# Output_Driver.net
KiCad netlist of a schematic drawn in Altium Designer
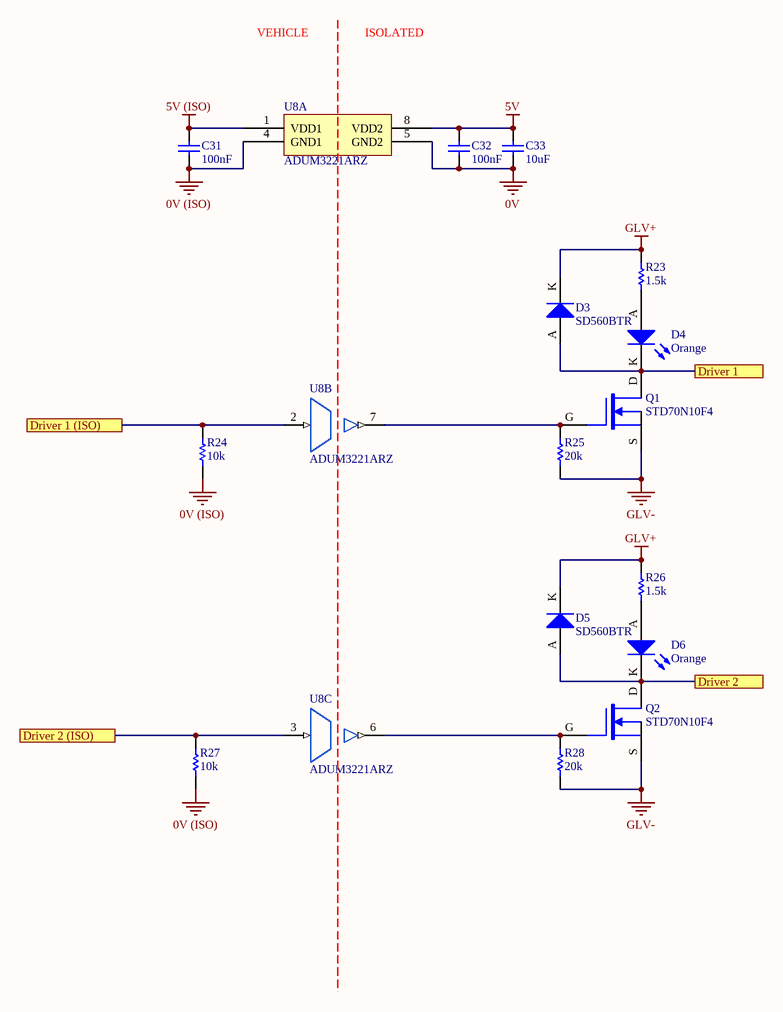
[diagram p0: Output Driver.SchDoc]

(export (version "E")
  (design (tool "Eeschema 10.0.6"))
  (components
    (comp (ref "C31")
      (value "100nF")
      (footprint "0805")
      (fields
        (field (name "PART NUMBER") "GCM21BR71E104KA37L")
        (field (name "TOLERANCE") "10%")
        (field (name "MANUFACTURER") "muRata")
      )
      (libsource (lib "ts_20-standard-library") (part "Capacitor"))
    )
    (comp (ref "C32")
      (value "100nF")
      (footprint "0805")
      (fields
        (field (name "PART NUMBER") "GCM21BR71E104KA37L")
        (field (name "TOLERANCE") "10%")
        (field (name "MANUFACTURER") "muRata")
      )
      (libsource (lib "ts_20-standard-library") (part "Capacitor"))
    )
    (comp (ref "C33")
      (value "10uF")
      (footprint "0805")
      (fields
        (field (name "PART NUMBER") "GRM21BR6YA106KE43L")
        (field (name "TOLERANCE") "10%")
        (field (name "MANUFACTURER") "muRata")
      )
      (libsource (lib "ts_20-standard-library") (part "Capacitor"))
    )
    (comp (ref "D3")
      (value "SD560BTR")
      (footprint "SMB Diode")
      (description "1.2V_F 600V 5A SMB")
      (fields
        (field (name "MANUFACTURER") "SMC Diode Solutions")
        (field (name "DIGIKEY PART NUMBER") "1655-1530-2-ND")
      )
      (libsource (lib "ts_20-standard-library") (part "Diode"))
    )
    (comp (ref "D4")
      (value "Orange")
      (footprint "0805 LED")
      (description "Orange LED Indication - Discrete 1.75V 0805 (2012 Metric)")
      (fields (field (name "PART NUMBER") "SML-211DTT86") (field (name "MANUFACTURER") "ROHM Semiconductor"))
      (libsource (lib "ts_20-standard-library") (part "LED"))
    )
    (comp (ref "D5")
      (value "SD560BTR")
      (footprint "SMB Diode")
      (description "1.2V_F 600V 5A SMB")
      (fields
        (field (name "MANUFACTURER") "SMC Diode Solutions")
        (field (name "DIGIKEY PART NUMBER") "1655-1530-2-ND")
      )
      (libsource (lib "ts_20-standard-library") (part "Diode"))
    )
    (comp (ref "D6")
      (value "Orange")
      (footprint "0805 LED")
      (description "Orange LED Indication - Discrete 1.75V 0805 (2012 Metric)")
      (fields (field (name "PART NUMBER") "SML-211DTT86") (field (name "MANUFACTURER") "ROHM Semiconductor"))
      (libsource (lib "ts_20-standard-library") (part "LED"))
    )
    (comp (ref "Q1")
      (value "STD70N10F4")
      (footprint "SOT-343_N")
      (description "N-Channel 100V 60A (Tc) 125W (Tc) Surface Mount DPAK")
      (fields
        (field (name "MANUFACTURER") "STMicroelectronics")
        (field (name "DIGIKEY PART NUMBER") "497-8806-2-ND")
        (field (name "PUBLISHER") "Altium Limited")
      )
      (libsource (lib "ts_20-standard-library") (part "MOSFET-N"))
    )
    (comp (ref "Q2")
      (value "STD70N10F4")
      (footprint "SOT-343_N")
      (description "N-Channel 100V 60A (Tc) 125W (Tc) Surface Mount DPAK")
      (fields
        (field (name "MANUFACTURER") "STMicroelectronics")
        (field (name "DIGIKEY PART NUMBER") "497-8806-2-ND")
        (field (name "PUBLISHER") "Altium Limited")
      )
      (libsource (lib "ts_20-standard-library") (part "MOSFET-N"))
    )
    (comp (ref "R23")
      (value "1.5k")
      (footprint "0805")
      (fields
        (field (name "PART NUMBER") "RC0805FR071K5L")
        (field (name "MANUFACTURER") "YAGEO")
        (field (name "TOLERANCE") "0.01")
      )
      (libsource (lib "ts_20-standard-library") (part "Resistor"))
    )
    (comp (ref "R24")
      (value "10k")
      (footprint "0805")
      (fields
        (field (name "PART NUMBER") "RC0805FR0710KL")
        (field (name "MANUFACTURER") "YAGEO")
        (field (name "TOLERANCE") "0.01")
      )
      (libsource (lib "ts_20-standard-library") (part "Resistor"))
    )
    (comp (ref "R25")
      (value "20k")
      (footprint "0805")
      (fields
        (field (name "PART NUMBER") "RC0805FR0720KL")
        (field (name "MANUFACTURER") "YAGEO")
        (field (name "TOLERANCE") "0.01")
      )
      (libsource (lib "ts_20-standard-library") (part "Resistor"))
    )
    (comp (ref "R26")
      (value "1.5k")
      (footprint "0805")
      (fields
        (field (name "PART NUMBER") "RC0805FR071K5L")
        (field (name "MANUFACTURER") "YAGEO")
        (field (name "TOLERANCE") "0.01")
      )
      (libsource (lib "ts_20-standard-library") (part "Resistor"))
    )
    (comp (ref "R27")
      (value "10k")
      (footprint "0805")
      (fields
        (field (name "PART NUMBER") "RC0805FR0710KL")
        (field (name "MANUFACTURER") "YAGEO")
        (field (name "TOLERANCE") "0.01")
      )
      (libsource (lib "ts_20-standard-library") (part "Resistor"))
    )
    (comp (ref "R28")
      (value "20k")
      (footprint "0805")
      (fields
        (field (name "PART NUMBER") "RC0805FR0720KL")
        (field (name "MANUFACTURER") "YAGEO")
        (field (name "TOLERANCE") "0.01")
      )
      (libsource (lib "ts_20-standard-library") (part "Resistor"))
    )
    (comp (ref "U8")
      (value "ADUM3221ARZ")
      (footprint "AD 8-SOIC")
      (description "4A Gate Driver Magnetic Coupling 2500Vrms 2 Channel 8-SOIC")
      (fields
        (field (name "MANUFACTURER") "Analog Devices")
        (field (name "DIGIKEY PART NUMBER") "ADUM3221ARZ-ND")
      )
      (libsource (lib "ts_20-standard-library") (part "ADuM3221"))
    )
  )
  (nets
    (net (code "1") (name "/Driver 1") (class "Default")
      (node (ref "D3") (pin "A") (pinfunction "A_A") (pintype "passive"))
      (node (ref "D4") (pin "K") (pinfunction "K_K") (pintype "passive"))
      (node (ref "Q1") (pin "D") (pinfunction "D_D") (pintype "passive"))
    )
    (net (code "2") (name "/Driver 1 (ISO)") (class "Default")
      (node (ref "R24") (pin "2") (pinfunction "2_2") (pintype "passive"))
      (node (ref "U8") (pin "2") (pinfunction "VIA_2") (pintype "input"))
    )
    (net (code "3") (name "/Driver 2") (class "Default")
      (node (ref "D5") (pin "A") (pinfunction "A_A") (pintype "passive"))
      (node (ref "D6") (pin "K") (pinfunction "K_K") (pintype "passive"))
      (node (ref "Q2") (pin "D") (pinfunction "D_D") (pintype "passive"))
    )
    (net (code "4") (name "/Driver 2 (ISO)") (class "Default")
      (node (ref "R27") (pin "2") (pinfunction "2_2") (pintype "passive"))
      (node (ref "U8") (pin "3") (pinfunction "VIA_3") (pintype "input"))
    )
    (net (code "5") (name "0V") (class "Default")
      (node (ref "C32") (pin "1") (pinfunction "1_1") (pintype "passive"))
      (node (ref "C33") (pin "1") (pinfunction "1_1") (pintype "passive"))
      (node (ref "U8") (pin "5") (pinfunction "GND2_5") (pintype "passive"))
    )
    (net (code "6") (name "0V (ISO)") (class "Default")
      (node (ref "C31") (pin "1") (pinfunction "1_1") (pintype "passive"))
      (node (ref "R24") (pin "1") (pinfunction "1_1") (pintype "passive"))
      (node (ref "R27") (pin "1") (pinfunction "1_1") (pintype "passive"))
      (node (ref "U8") (pin "4") (pinfunction "GND1_4") (pintype "passive"))
    )
    (net (code "7") (name "5V") (class "Default")
      (node (ref "C32") (pin "2") (pinfunction "2_2") (pintype "passive"))
      (node (ref "C33") (pin "2") (pinfunction "2_2") (pintype "passive"))
      (node (ref "U8") (pin "8") (pinfunction "VDD2_8") (pintype "passive"))
    )
    (net (code "8") (name "5V (ISO)") (class "Default")
      (node (ref "C31") (pin "2") (pinfunction "2_2") (pintype "passive"))
      (node (ref "U8") (pin "1") (pinfunction "VDD1_1") (pintype "passive"))
    )
    (net (code "9") (name "GLV+") (class "Default")
      (node (ref "D3") (pin "K") (pinfunction "K_K") (pintype "passive"))
      (node (ref "D5") (pin "K") (pinfunction "K_K") (pintype "passive"))
      (node (ref "R23") (pin "2") (pinfunction "2_2") (pintype "passive"))
      (node (ref "R26") (pin "2") (pinfunction "2_2") (pintype "passive"))
    )
    (net (code "10") (name "GLV-") (class "Default")
      (node (ref "Q1") (pin "S") (pinfunction "S_S") (pintype "passive"))
      (node (ref "Q2") (pin "S") (pinfunction "S_S") (pintype "passive"))
      (node (ref "R25") (pin "1") (pinfunction "1_1") (pintype "passive"))
      (node (ref "R28") (pin "1") (pinfunction "1_1") (pintype "passive"))
    )
    (net (code "11") (name "Net-(D4-PadA)") (class "Default")
      (node (ref "D4") (pin "A") (pinfunction "A_A") (pintype "passive"))
      (node (ref "R23") (pin "1") (pinfunction "1_1") (pintype "passive"))
    )
    (net (code "12") (name "Net-(D6-PadA)") (class "Default")
      (node (ref "D6") (pin "A") (pinfunction "A_A") (pintype "passive"))
      (node (ref "R26") (pin "1") (pinfunction "1_1") (pintype "passive"))
    )
    (net (code "13") (name "Net-(U8B-VOA)") (class "Default")
      (node (ref "Q1") (pin "G") (pinfunction "G_G") (pintype "passive"))
      (node (ref "R25") (pin "2") (pinfunction "2_2") (pintype "passive"))
      (node (ref "U8") (pin "7") (pinfunction "VOA_7") (pintype "output"))
    )
    (net (code "14") (name "Net-(U8C-VOA)") (class "Default")
      (node (ref "Q2") (pin "G") (pinfunction "G_G") (pintype "passive"))
      (node (ref "R28") (pin "2") (pinfunction "2_2") (pintype "passive"))
      (node (ref "U8") (pin "6") (pinfunction "VOA_6") (pintype "output"))
    )
  )
)
